# PCB_Proyecto_Analoga.net
KiCad netlist of a schematic drawn in Altium Designer
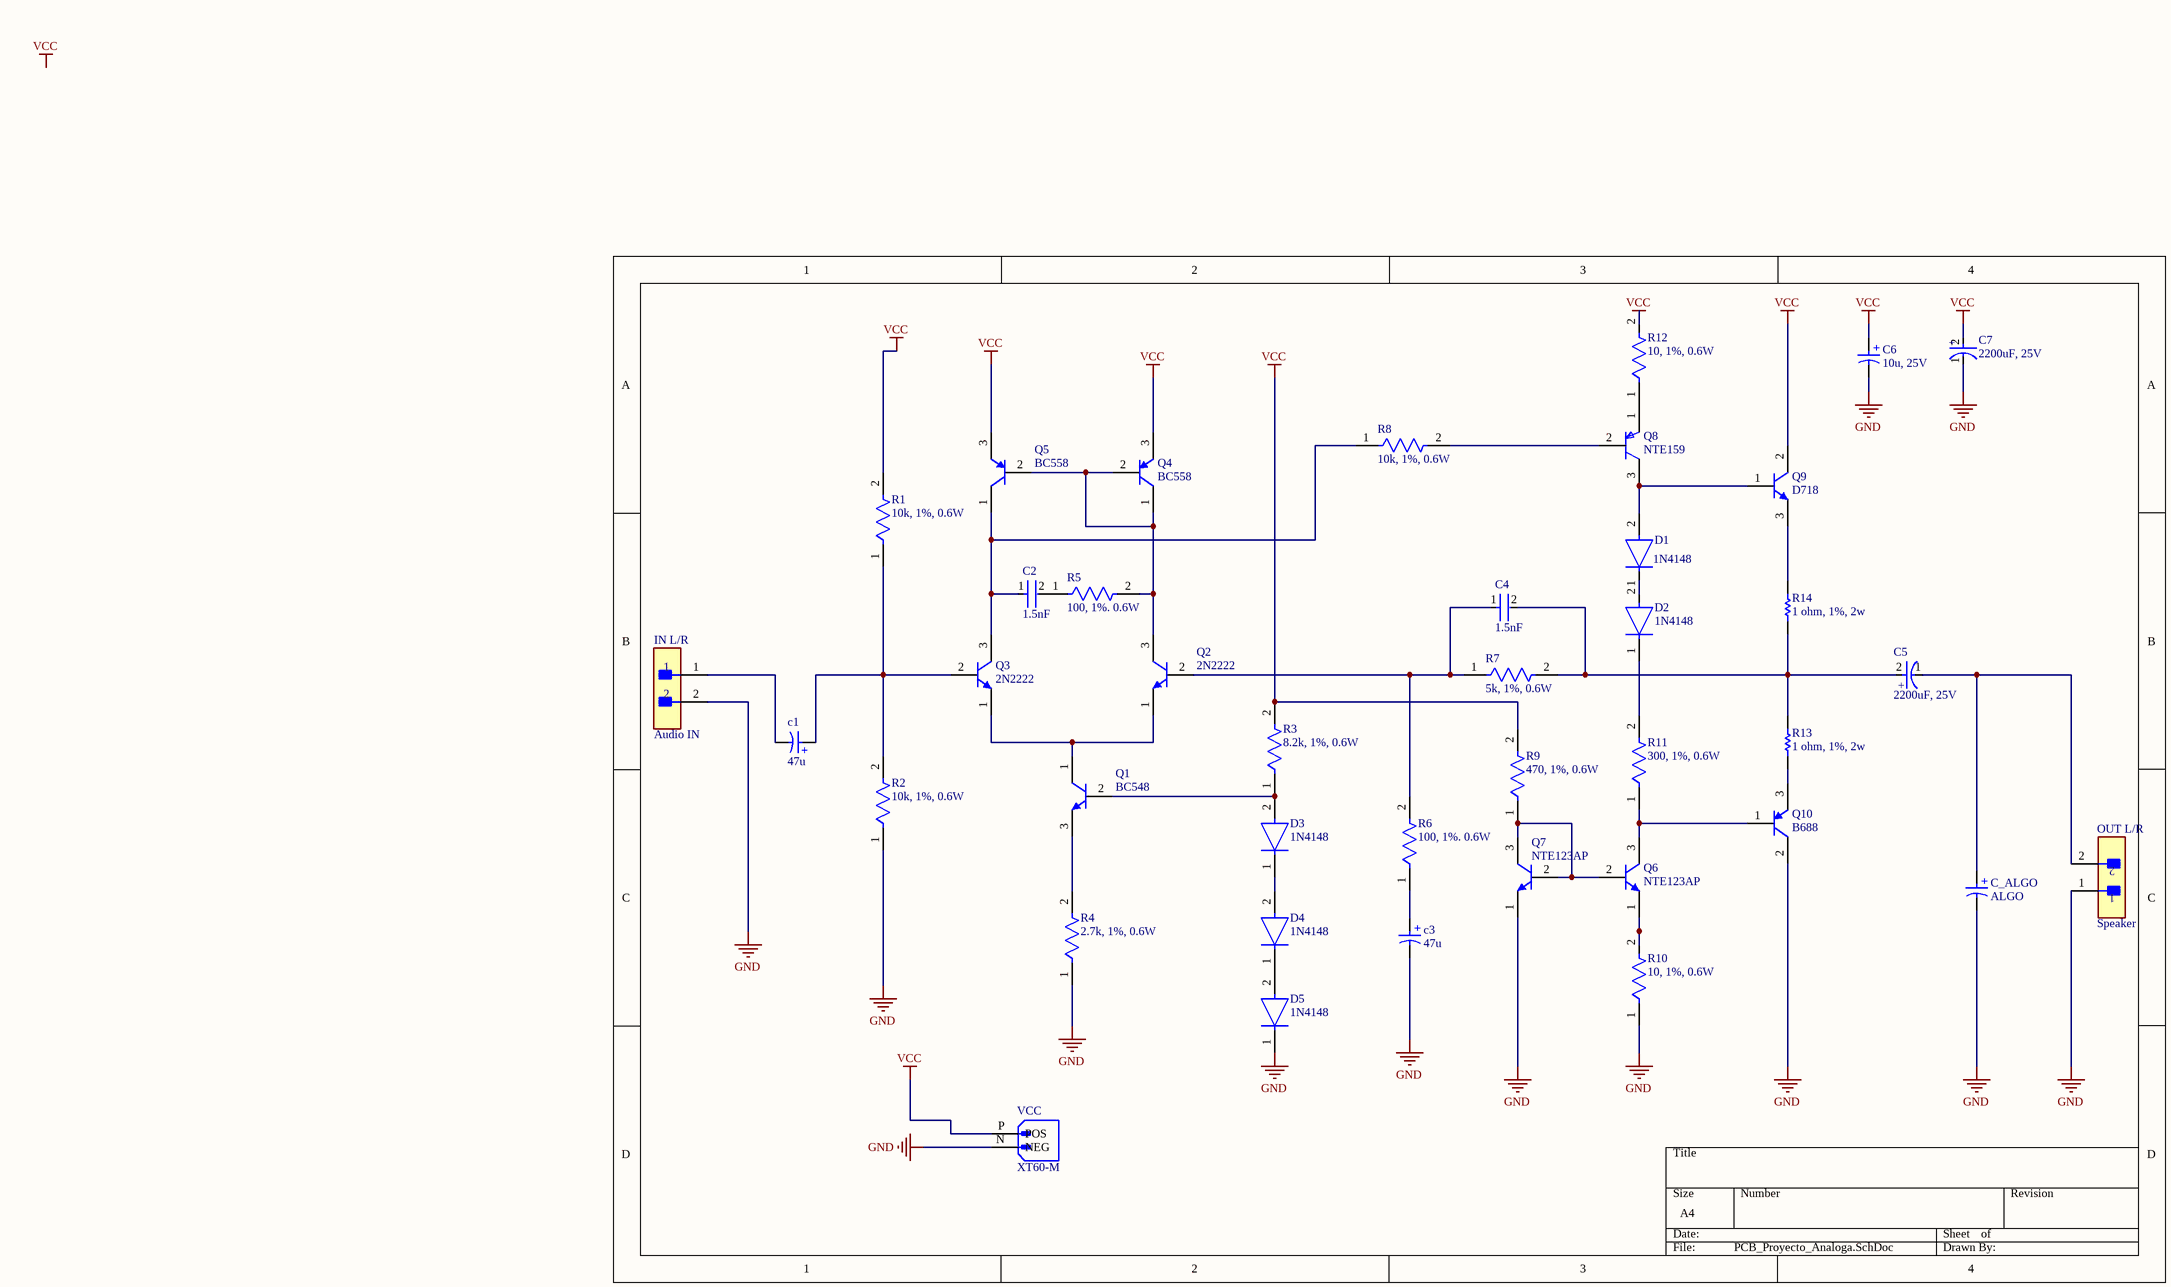
[diagram p0: PCB_Proyecto_Analoga.SchDoc]

(export (version "E")
  (design (tool "Eeschema 10.0.6"))
  (components
    (comp (ref "c1")
      (value "47u")
      (footprint "WCAP-ATG5_D5H11")
      (description "860020472003 WCAP-ATG5 Aluminum Electrolytic Capacitors")
      (fields (field (name "TOLERANCE") "20%"))
      (libsource (lib "Altium Content Vault") (part "Capacitor_Polarized"))
    )
    (comp (ref "C2")
      (value "1.5nF")
      (footprint "FP-K105Z20Y5VF5TL2-MFG")
      (description "CAP CER 1UF 50V Y5V RADIAL")
      (fields
        (field (name "TOLERANCE") "-20+80%")
        (field (name "OCTOPART") "https://octopart.com/k105z20y5vf5tl2-vishay-39475252")
      )
      (libsource (lib "Altium Content Vault") (part "11868f565c42a9108669ba33697ecf6"))
    )
    (comp (ref "c3")
      (value "47u")
      (footprint "WCAP-ATG5_D5H11")
      (description "860020472003 WCAP-ATG5 Aluminum Electrolytic Capacitors")
      (fields (field (name "TOLERANCE") "20%"))
      (libsource (lib "Altium Content Vault") (part "Capacitor_Polarized"))
    )
    (comp (ref "C4")
      (value "1.5nF")
      (footprint "FP-K105Z20Y5VF5TL2-MFG")
      (description "CAP CER 1UF 50V Y5V RADIAL")
      (fields
        (field (name "TOLERANCE") "-20+80%")
        (field (name "OCTOPART") "https://octopart.com/k105z20y5vf5tl2-vishay-39475252")
      )
      (libsource (lib "Altium Content Vault") (part "11868f565c42a9108669ba33697ecf6"))
    )
    (comp (ref "C5")
      (value "2200uF, 25V")
      (footprint "FP-RAD-TH-D_12_5_0_5-L_35-MFG")
      (description "Aluminum Electrolytic Capacitors (Radial Lead Type) AEC-Q200 Qualified 2200uF ±20% 25V")
      (fields (field (name "VOLTAGE") "25V") (field (name "TOLERANCE") "20%"))
      (libsource (lib "Altium Content Vault") (part "a00bbbee19879c290e62620ae7e47b1"))
    )
    (comp (ref "C6")
      (value "10u, 25V")
      (footprint "WCAP-ATG5_D5H11")
      (description "860020472003 WCAP-ATG5 Aluminum Electrolytic Capacitors")
      (fields (field (name "TOLERANCE") "20%"))
      (libsource (lib "Altium Content Vault") (part "Capacitor_Polarized"))
    )
    (comp (ref "C7")
      (value "2200uF, 25V")
      (footprint "FP-RAD-TH-D_12_5_0_5-L_35-MFG")
      (description "Aluminum Electrolytic Capacitors (Radial Lead Type) AEC-Q200 Qualified 2200uF ±20% 25V")
      (fields (field (name "VOLTAGE") "25V") (field (name "TOLERANCE") "20%"))
      (libsource (lib "Altium Content Vault") (part "a00bbbee19879c290e62620ae7e47b1"))
    )
    (comp (ref "C_ALGO")
      (value "ALGO")
      (footprint "WCAP-ATG5_D5H11")
      (description "860020472003 WCAP-ATG5 Aluminum Electrolytic Capacitors")
      (fields (field (name "TOLERANCE") "20%"))
      (libsource (lib "Altium Content Vault") (part "Capacitor_Polarized"))
    )
    (comp (ref "D1")
      (value "1N4148")
      (footprint "FP-DO-35-MFG")
      (description "DIODE GEN PURP 75V 200MA DO35")
      (libsource (lib "Altium Content Vault") (part "d7152d700b627762746794eb795d46e"))
    )
    (comp (ref "D2")
      (value "1N4148")
      (footprint "FP-DO-35-MFG")
      (description "DIODE GEN PURP 75V 200MA DO35")
      (libsource (lib "Altium Content Vault") (part "d7152d700b627762746794eb795d46e"))
    )
    (comp (ref "D3")
      (value "1N4148")
      (footprint "FP-DO-35-MFG")
      (description "DIODE GEN PURP 75V 200MA DO35")
      (libsource (lib "Altium Content Vault") (part "d7152d700b627762746794eb795d46e"))
    )
    (comp (ref "D4")
      (value "1N4148")
      (footprint "FP-DO-35-MFG")
      (description "DIODE GEN PURP 75V 200MA DO35")
      (libsource (lib "Altium Content Vault") (part "d7152d700b627762746794eb795d46e"))
    )
    (comp (ref "D5")
      (value "1N4148")
      (footprint "FP-DO-35-MFG")
      (description "DIODE GEN PURP 75V 200MA DO35")
      (libsource (lib "Altium Content Vault") (part "d7152d700b627762746794eb795d46e"))
    )
    (comp (ref "IN L/R")
      (value "Audio IN")
      (footprint "FP-22-28-8020-MFG")
      (libsource (lib "") (part "3bc925449376181038e59eaffc5286c_1"))
    )
    (comp (ref "OUT L/R")
      (value "Speaker")
      (footprint "FP-22-28-8020-MFG")
      (libsource (lib "Altium Content Vault") (part "3bc925449376181038e59eaffc5286c"))
    )
    (comp (ref "Q1")
      (value "BC548")
      (footprint "ONSC-TO-92-3-29-11_AM_BL")
      (description "Amplifier Transistor, NPN Silicon, 3-Pin TO-92, Pb-Free, Tape and Reel")
      (fields (field (name "MANUFACTURER") "On Semiconductor") (field (name "PARTNUMBER") "BC548BRL1G"))
      (libsource (lib "Altium Content Vault") (part "ONSC-NPN-C1B2E3-3"))
    )
    (comp (ref "Q2")
      (value "2N2222")
      (footprint "FAIR-TO-92-3")
      (description "NPN General-Purpose Amplifier, 40 V, -55 to 150 degC, 3-Pin TO-92, RoHS, Tape and Reel")
      (fields (field (name "MANUFACTURER") "FairchildSemiconductor"))
      (libsource (lib "Altium Content Vault") (part "BJT-NPN-EBC-3"))
    )
    (comp (ref "Q3")
      (value "2N2222")
      (footprint "FAIR-TO-92-3")
      (description "NPN General-Purpose Amplifier, 40 V, -55 to 150 degC, 3-Pin TO-92, RoHS, Tape and Reel")
      (fields (field (name "MANUFACTURER") "FairchildSemiconductor"))
      (libsource (lib "Altium Content Vault") (part "BJT-NPN-EBC-3"))
    )
    (comp (ref "Q4")
      (value "BC558")
      (footprint "ONSC-TO-92-3-29-11_AM_BL")
      (description "Amplifier Transistor, PNP Silicon, 3-Pin TO-92, Pb-Free, Tape and Reel")
      (fields (field (name "MANUFACTURER") "On Semiconductor") (field (name "PARTNUMBER") "BC558BRL1G"))
      (libsource (lib "Altium Content Vault") (part "ONSC-PNP-C1B2E3-3"))
    )
    (comp (ref "Q5")
      (value "BC558")
      (footprint "ONSC-TO-92-3-29-11_AM_BL")
      (description "Amplifier Transistor, PNP Silicon, 3-Pin TO-92, Pb-Free, Tape and Reel")
      (fields (field (name "MANUFACTURER") "On Semiconductor") (field (name "PARTNUMBER") "BC558BRL1G"))
      (libsource (lib "Altium Content Vault") (part "ONSC-PNP-C1B2E3-3"))
    )
    (comp (ref "Q6")
      (value "NTE123AP")
      (footprint "FAIR-TO-92-3")
      (description "NPN General-Purpose Amplifier, 40 V, -55 to 150 degC, 3-Pin TO-92, RoHS, Tape and Reel")
      (fields (field (name "MANUFACTURER") "FairchildSemiconductor"))
      (libsource (lib "Altium Content Vault") (part "BJT-NPN-EBC-3"))
    )
    (comp (ref "Q7")
      (value "NTE123AP")
      (footprint "FAIR-TO-92-3")
      (description "NPN General-Purpose Amplifier, 40 V, -55 to 150 degC, 3-Pin TO-92, RoHS, Tape and Reel")
      (fields (field (name "MANUFACTURER") "FairchildSemiconductor"))
      (libsource (lib "Altium Content Vault") (part "BJT-NPN-EBC-3"))
    )
    (comp (ref "Q8")
      (value "NTE159")
      (footprint "FP-135AR-MFG")
      (description "2N3906TF Small Signal Bipolar Transistor, 0.2A I(C), 40V V(BR)CEO, 1-Element, PNP, Silicon, TO-92")
      (libsource (lib "Altium Content Vault") (part "40d2b7e180a7bcff784209620afba3e"))
    )
    (comp (ref "Q9")
      (value "D718")
      (footprint "ONSC-TO-3P-3LD-3-340AB-01")
      (description "Complementary NPN Silicon Power Bipolar Transistor, 3-Pin TO-3P-3LD, Pb-Free, Tube")
      (fields (field (name "PARTNUMBER") "NJW3281G") (field (name "MANUFACTURER") "On Semiconductor"))
      (libsource (lib "Altium Content Vault") (part "ONSC-NPN-B1C2E3-3_C"))
    )
    (comp (ref "Q10")
      (value "B688")
      (footprint "ONSC-TO-3P-3LD-3-340AB-01")
      (description "Complementary PNP Silicon Power Bipolar Transistor, 3-Pin TO-3P-3LD, Pb-Free, Tube")
      (fields (field (name "PARTNUMBER") "NJW1302G") (field (name "MANUFACTURER") "On Semiconductor"))
      (libsource (lib "Altium Content Vault") (part "ONSC-PNP-B1C2E3-3"))
    )
    (comp (ref "R1")
      (value "10k, 1%, 0.6W")
      (footprint "FP-MF0207-MFG")
      (description "RES 10K OHM 1% 0.6W AXIAL")
      (fields (field (name "TOLERANCE") "1%"))
      (libsource (lib "Altium Content Vault") (part "1029c3af85768c4190bb7ad29bc67b5"))
    )
    (comp (ref "R2")
      (value "10k, 1%, 0.6W")
      (footprint "FP-MF0207-MFG")
      (description "RES 10K OHM 1% 0.6W AXIAL")
      (fields (field (name "TOLERANCE") "1%"))
      (libsource (lib "Altium Content Vault") (part "1029c3af85768c4190bb7ad29bc67b5"))
    )
    (comp (ref "R3")
      (value "8.2k, 1%, 0.6W")
      (footprint "FP-MRS25-MFG")
      (description "RES 953 OHM 0.6W 1% AXIAL")
      (fields (field (name "TOLERANCE") "1%"))
      (libsource (lib "Altium Content Vault") (part "1029c3af85768c4190bb7ad29bc67b5"))
    )
    (comp (ref "R4")
      (value "2.7k, 1%, 0.6W")
      (footprint "FP-MF0207-MFG")
      (description "RES 10K OHM 1% 0.6W AXIAL")
      (fields (field (name "TOLERANCE") "1%"))
      (libsource (lib "Altium Content Vault") (part "1029c3af85768c4190bb7ad29bc67b5"))
    )
    (comp (ref "R5")
      (value "100, 1%. 0.6W")
      (footprint "FP-MRS25-MFG")
      (fields (field (name "TOLERANCE") "1%"))
      (libsource (lib "Altium Content Vault") (part "1029c3af85768c4190bb7ad29bc67b5"))
    )
    (comp (ref "R6")
      (value "100, 1%. 0.6W")
      (footprint "FP-MRS25-MFG")
      (fields (field (name "TOLERANCE") "1%"))
      (libsource (lib "Altium Content Vault") (part "1029c3af85768c4190bb7ad29bc67b5"))
    )
    (comp (ref "R7")
      (value "5k, 1%, 0.6W")
      (footprint "FP-MF0207-MFG")
      (description "RES 10K OHM 1% 0.6W AXIAL")
      (fields (field (name "TOLERANCE") "1%"))
      (libsource (lib "Altium Content Vault") (part "1029c3af85768c4190bb7ad29bc67b5"))
    )
    (comp (ref "R8")
      (value "10k, 1%, 0.6W")
      (footprint "FP-MF0207-MFG")
      (description "RES 10K OHM 1% 0.6W AXIAL")
      (fields (field (name "TOLERANCE") "1%"))
      (libsource (lib "Altium Content Vault") (part "1029c3af85768c4190bb7ad29bc67b5"))
    )
    (comp (ref "R9")
      (value "470, 1%, 0.6W")
      (footprint "FP-MRS25-MFG")
      (description "RES 1K OHM 0.6W 1% AXIAL")
      (fields (field (name "TOLERANCE") "1%"))
      (libsource (lib "Altium Content Vault") (part "1029c3af85768c4190bb7ad29bc67b5"))
    )
    (comp (ref "R10")
      (value "10, 1%, 0.6W")
      (footprint "FP-MRS25-MFG")
      (fields (field (name "TOLERANCE") "1%"))
      (libsource (lib "Altium Content Vault") (part "1029c3af85768c4190bb7ad29bc67b5"))
    )
    (comp (ref "R11")
      (value "300, 1%, 0.6W")
      (footprint "FP-MF0207-MFG")
      (description "RES 10K OHM 1% 0.6W AXIAL")
      (fields (field (name "TOLERANCE") "1%"))
      (libsource (lib "Altium Content Vault") (part "1029c3af85768c4190bb7ad29bc67b5"))
    )
    (comp (ref "R12")
      (value "10, 1%, 0.6W")
      (footprint "FP-MRS25-MFG")
      (fields (field (name "TOLERANCE") "1%"))
      (libsource (lib "Altium Content Vault") (part "1029c3af85768c4190bb7ad29bc67b5"))
    )
    (comp (ref "R13")
      (value "1 ohm, 1%, 2w")
      (footprint "RESA86-1060X240")
      (description "Axial Resistor, 50 mOhm, +/- 1%, 2 W, -55 to 275 degC, 2-Pin THD, RoHS, Bulk")
      (libsource (lib "Altium Content Vault") (part "RES-2"))
    )
    (comp (ref "R14")
      (value "1 ohm, 1%, 2w")
      (footprint "RESA86-1060X240")
      (description "Axial Resistor, 50 mOhm, +/- 1%, 2 W, -55 to 275 degC, 2-Pin THD, RoHS, Bulk")
      (libsource (lib "Altium Content Vault") (part "RES-2"))
    )
    (comp (ref "VCC")
      (value "XT60-M")
      (footprint "AMASS_XT60-M")
      (description "Plug; DC supply; XT60; male; PIN: 2; for cable; soldered; 30A; 500V")
      (fields (field (name "MF") "AMASS"))
      (libsource (lib "Universidad de los Andes") (part "XT60-M"))
    )
  )
  (nets
    (net (code "1") (name "GND") (class "Default")
      (node (ref "C6") (pin "2") (pinfunction "N_2") (pintype "passive"))
      (node (ref "C7") (pin "1") (pinfunction "C_1") (pintype "passive"))
      (node (ref "C_ALGO") (pin "2") (pinfunction "N_2") (pintype "passive"))
      (node (ref "D5") (pin "1") (pinfunction "C_1") (pintype "passive"))
      (node (ref "IN L/R") (pin "2") (pinfunction "2_2") (pintype "passive"))
      (node (ref "OUT L/R") (pin "1") (pinfunction "1_1") (pintype "passive"))
      (node (ref "Q10") (pin "2") (pinfunction "C_2") (pintype "passive"))
      (node (ref "Q7") (pin "1") (pinfunction "E_1") (pintype "passive"))
      (node (ref "R10") (pin "1") (pinfunction "1_1") (pintype "passive"))
      (node (ref "R2") (pin "1") (pinfunction "1_1") (pintype "passive"))
      (node (ref "R4") (pin "1") (pinfunction "1_1") (pintype "passive"))
      (node (ref "VCC") (pin "N") (pinfunction "NEG_N") (pintype "passive"))
      (node (ref "c3") (pin "2") (pinfunction "N_2") (pintype "passive"))
    )
    (net (code "2") (name "Net-(C2-Pad2)") (class "Default")
      (node (ref "C2") (pin "2") (pinfunction "2_2") (pintype "passive"))
      (node (ref "R5") (pin "1") (pinfunction "1_1") (pintype "passive"))
    )
    (net (code "3") (name "Net-(C5-A)") (class "Default")
      (node (ref "C4") (pin "2") (pinfunction "2_2") (pintype "passive"))
      (node (ref "C5") (pin "2") (pinfunction "A_2") (pintype "passive"))
      (node (ref "R13") (pin "2") (pinfunction "2_2") (pintype "passive"))
      (node (ref "R14") (pin "1") (pinfunction "1_1") (pintype "passive"))
      (node (ref "R7") (pin "2") (pinfunction "2_2") (pintype "passive"))
    )
    (net (code "4") (name "Net-(C5-C)") (class "Default")
      (node (ref "C5") (pin "1") (pinfunction "C_1") (pintype "passive"))
      (node (ref "C_ALGO") (pin "1") (pinfunction "P_1") (pintype "passive"))
      (node (ref "OUT L/R") (pin "2") (pinfunction "2_2") (pintype "passive"))
    )
    (net (code "5") (name "Net-(D1-A)") (class "Default")
      (node (ref "D1") (pin "2") (pinfunction "A_2") (pintype "passive"))
      (node (ref "Q8") (pin "3") (pinfunction "C_3") (pintype "passive"))
      (node (ref "Q9") (pin "1") (pinfunction "B_1") (pintype "passive"))
    )
    (net (code "6") (name "Net-(D1-C)") (class "Default")
      (node (ref "D1") (pin "1") (pinfunction "C_1") (pintype "passive"))
      (node (ref "D2") (pin "2") (pinfunction "A_2") (pintype "passive"))
    )
    (net (code "7") (name "Net-(D2-C)") (class "Default")
      (node (ref "D2") (pin "1") (pinfunction "C_1") (pintype "passive"))
      (node (ref "R11") (pin "2") (pinfunction "2_2") (pintype "passive"))
    )
    (net (code "8") (name "Net-(D3-A)") (class "Default")
      (node (ref "D3") (pin "2") (pinfunction "A_2") (pintype "passive"))
      (node (ref "Q1") (pin "2") (pinfunction "B_2") (pintype "passive"))
      (node (ref "R3") (pin "1") (pinfunction "1_1") (pintype "passive"))
    )
    (net (code "9") (name "Net-(D3-C)") (class "Default")
      (node (ref "D3") (pin "1") (pinfunction "C_1") (pintype "passive"))
      (node (ref "D4") (pin "2") (pinfunction "A_2") (pintype "passive"))
    )
    (net (code "10") (name "Net-(D4-C)") (class "Default")
      (node (ref "D4") (pin "1") (pinfunction "C_1") (pintype "passive"))
      (node (ref "D5") (pin "2") (pinfunction "A_2") (pintype "passive"))
    )
    (net (code "11") (name "Net-(Q1-C)") (class "Default")
      (node (ref "Q1") (pin "1") (pinfunction "C_1") (pintype "passive"))
      (node (ref "Q2") (pin "1") (pinfunction "E_1") (pintype "passive"))
      (node (ref "Q3") (pin "1") (pinfunction "E_1") (pintype "passive"))
    )
    (net (code "12") (name "Net-(Q1-E)") (class "Default")
      (node (ref "Q1") (pin "3") (pinfunction "E_3") (pintype "passive"))
      (node (ref "R4") (pin "2") (pinfunction "2_2") (pintype "passive"))
    )
    (net (code "13") (name "Net-(Q2-B)") (class "Default")
      (node (ref "C4") (pin "1") (pinfunction "1_1") (pintype "passive"))
      (node (ref "Q2") (pin "2") (pinfunction "B_2") (pintype "passive"))
      (node (ref "R6") (pin "2") (pinfunction "2_2") (pintype "passive"))
      (node (ref "R7") (pin "1") (pinfunction "1_1") (pintype "passive"))
    )
    (net (code "14") (name "Net-(Q2-C)") (class "Default")
      (node (ref "Q2") (pin "3") (pinfunction "C_3") (pintype "passive"))
      (node (ref "Q4") (pin "1") (pinfunction "C_1") (pintype "passive"))
      (node (ref "Q4") (pin "2") (pinfunction "B_2") (pintype "passive"))
      (node (ref "Q5") (pin "2") (pinfunction "B_2") (pintype "passive"))
      (node (ref "R5") (pin "2") (pinfunction "2_2") (pintype "passive"))
    )
    (net (code "15") (name "Net-(Q3-B)") (class "Default")
      (node (ref "Q3") (pin "2") (pinfunction "B_2") (pintype "passive"))
      (node (ref "R1") (pin "1") (pinfunction "1_1") (pintype "passive"))
      (node (ref "R2") (pin "2") (pinfunction "2_2") (pintype "passive"))
      (node (ref "c1") (pin "1") (pinfunction "P_1") (pintype "passive"))
    )
    (net (code "16") (name "Net-(Q3-C)") (class "Default")
      (node (ref "C2") (pin "1") (pinfunction "1_1") (pintype "passive"))
      (node (ref "Q3") (pin "3") (pinfunction "C_3") (pintype "passive"))
      (node (ref "Q5") (pin "1") (pinfunction "C_1") (pintype "passive"))
      (node (ref "R8") (pin "1") (pinfunction "1_1") (pintype "passive"))
    )
    (net (code "17") (name "Net-(Q6-B)") (class "Default")
      (node (ref "Q6") (pin "2") (pinfunction "B_2") (pintype "passive"))
      (node (ref "Q7") (pin "2") (pinfunction "B_2") (pintype "passive"))
      (node (ref "Q7") (pin "3") (pinfunction "C_3") (pintype "passive"))
      (node (ref "R9") (pin "1") (pinfunction "1_1") (pintype "passive"))
    )
    (net (code "18") (name "Net-(Q6-E)") (class "Default")
      (node (ref "Q6") (pin "1") (pinfunction "E_1") (pintype "passive"))
      (node (ref "R10") (pin "2") (pinfunction "2_2") (pintype "passive"))
    )
    (net (code "19") (name "Net-(Q8-B)") (class "Default")
      (node (ref "Q8") (pin "2") (pinfunction "B_2") (pintype "passive"))
      (node (ref "R8") (pin "2") (pinfunction "2_2") (pintype "passive"))
    )
    (net (code "20") (name "Net-(Q8-E)") (class "Default")
      (node (ref "Q8") (pin "1") (pinfunction "E_1") (pintype "passive"))
      (node (ref "R12") (pin "1") (pinfunction "1_1") (pintype "passive"))
    )
    (net (code "21") (name "Net-(Q9-E)") (class "Default")
      (node (ref "Q9") (pin "3") (pinfunction "E_3") (pintype "passive"))
      (node (ref "R14") (pin "2") (pinfunction "2_2") (pintype "passive"))
    )
    (net (code "22") (name "Net-(Q10-B)") (class "Default")
      (node (ref "Q10") (pin "1") (pinfunction "B_1") (pintype "passive"))
      (node (ref "Q6") (pin "3") (pinfunction "C_3") (pintype "passive"))
      (node (ref "R11") (pin "1") (pinfunction "1_1") (pintype "passive"))
    )
    (net (code "23") (name "Net-(Q10-E)") (class "Default")
      (node (ref "Q10") (pin "3") (pinfunction "E_3") (pintype "passive"))
      (node (ref "R13") (pin "1") (pinfunction "1_1") (pintype "passive"))
    )
    (net (code "24") (name "Net-(c1-N)") (class "Default")
      (node (ref "IN L/R") (pin "1") (pinfunction "1_1") (pintype "passive"))
      (node (ref "c1") (pin "2") (pinfunction "N_2") (pintype "passive"))
    )
    (net (code "25") (name "Net-(c3-P)") (class "Default")
      (node (ref "R6") (pin "1") (pinfunction "1_1") (pintype "passive"))
      (node (ref "c3") (pin "1") (pinfunction "P_1") (pintype "passive"))
    )
    (net (code "26") (name "VCC") (class "Default")
      (node (ref "C6") (pin "1") (pinfunction "P_1") (pintype "passive"))
      (node (ref "C7") (pin "2") (pinfunction "A_2") (pintype "passive"))
      (node (ref "Q4") (pin "3") (pinfunction "E_3") (pintype "passive"))
      (node (ref "Q5") (pin "3") (pinfunction "E_3") (pintype "passive"))
      (node (ref "Q9") (pin "2") (pinfunction "C_2") (pintype "passive"))
      (node (ref "R1") (pin "2") (pinfunction "2_2") (pintype "passive"))
      (node (ref "R12") (pin "2") (pinfunction "2_2") (pintype "passive"))
      (node (ref "R3") (pin "2") (pinfunction "2_2") (pintype "passive"))
      (node (ref "R9") (pin "2") (pinfunction "2_2") (pintype "passive"))
      (node (ref "VCC") (pin "P") (pinfunction "POS_P") (pintype "passive"))
    )
  )
)
